# CDCDCDC_5V.net
KiCad netlist of a schematic drawn in Altium Designer
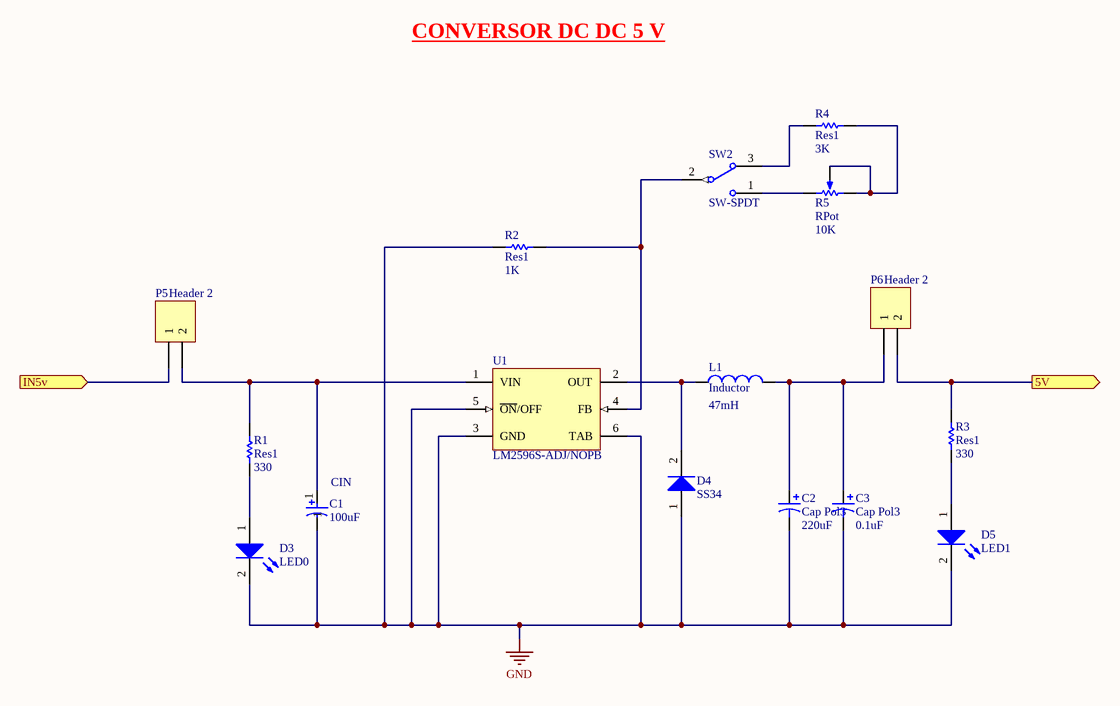
[diagram p0: CDCDCDC_5V.SchDoc]

(export (version "E")
  (design (tool "Eeschema 10.0.6"))
  (components
    (comp (ref "C1")
      (value "100uF")
      (footprint "NIC-UWT1H101MNL1GS_N")
      (fields (field (name "MANUFACTURER") "Nichicon"))
      (libsource (lib "Schlib1") (part "CMP-2000-07373-1"))
    )
    (comp (ref "C2")
      (value "Cap Pol3")
      (footprint "1812")
      (description "Polarized Capacitor (Surface Mount)")
      (fields (field (name "ALTIUM_VALUE") "220uF") (field (name "PUBLISHER") "Altium Limited"))
      (libsource (lib "Miscellaneous Devices") (part "Cap Pol3"))
    )
    (comp (ref "C3")
      (value "Cap Pol3")
      (footprint "1812")
      (description "Polarized Capacitor (Surface Mount)")
      (fields (field (name "ALTIUM_VALUE") "0.1uF") (field (name "PUBLISHER") "Altium Limited"))
      (libsource (lib "Miscellaneous Devices") (part "Cap Pol3"))
    )
    (comp (ref "D3")
      (value "LED0")
      (footprint "LED-0")
      (description "Typical INFRARED GaAs LED")
      (fields (field (name "PUBLISHER") "Altium Limited"))
      (libsource (lib "Miscellaneous Devices") (part "LED0"))
    )
    (comp (ref "D4")
      (value "SS34")
      (footprint "SMC")
      (description "Default Diode")
      (fields (field (name "PUBLISHER") "Altium Limited"))
      (libsource (lib "Miscellaneous Devices") (part "Diode"))
    )
    (comp (ref "D5")
      (value "LED1")
      (footprint "LED-0")
      (description "Typical INFRARED GaAs LED")
      (fields (field (name "PUBLISHER") "Altium Limited"))
      (libsource (lib "Miscellaneous Devices") (part "LED0"))
    )
    (comp (ref "L1")
      (value "Inductor")
      (footprint "0402-A")
      (fields (field (name "ALTIUM_VALUE") "47mH") (field (name "PUBLISHER") "Altium Limited"))
      (libsource (lib "Miscellaneous Devices") (part "Inductor"))
    )
    (comp (ref "P5")
      (value "Header 2")
      (footprint "HDR1X2")
      (description "Header, 2-Pin")
      (fields (field (name "PUBLISHER") "Altium Limited"))
      (libsource (lib "Miscellaneous Connectors") (part "Header 2"))
    )
    (comp (ref "P6")
      (value "Header 2")
      (footprint "HDR1X2")
      (description "Header, 2-Pin")
      (fields (field (name "PUBLISHER") "Altium Limited"))
      (libsource (lib "Miscellaneous Connectors") (part "Header 2"))
    )
    (comp (ref "R1")
      (value "Res1")
      (footprint "AXIAL-0.3")
      (description "Resistor")
      (fields (field (name "ALTIUM_VALUE") "330") (field (name "PUBLISHER") "Altium Limited"))
      (libsource (lib "Miscellaneous Devices") (part "Res1"))
    )
    (comp (ref "R2")
      (value "Res1")
      (footprint "AXIAL-0.3")
      (description "Resistor")
      (fields (field (name "ALTIUM_VALUE") "1K") (field (name "PUBLISHER") "Altium Limited"))
      (libsource (lib "Miscellaneous Devices") (part "Res1"))
    )
    (comp (ref "R3")
      (value "Res1")
      (footprint "AXIAL-0.3")
      (description "Resistor")
      (fields (field (name "ALTIUM_VALUE") "330") (field (name "PUBLISHER") "Altium Limited"))
      (libsource (lib "Miscellaneous Devices") (part "Res1"))
    )
    (comp (ref "R4")
      (value "Res1")
      (footprint "AXIAL-0.3")
      (description "Resistor")
      (fields (field (name "ALTIUM_VALUE") "3K") (field (name "PUBLISHER") "Altium Limited"))
      (libsource (lib "Miscellaneous Devices") (part "Res1"))
    )
    (comp (ref "R5")
      (value "RPot")
      (footprint "VR5")
      (description "Potentiometer")
      (fields (field (name "ALTIUM_VALUE") "10K") (field (name "PUBLISHER") "Altium Limited"))
      (libsource (lib "Miscellaneous Devices") (part "RPot"))
    )
    (comp (ref "SW2")
      (value "SW-SPDT")
      (footprint "TL36WW15050")
      (description "SPDT Subminiature Toggle Switch, Right Angle Mounting, Vertical Actuation")
      (fields (field (name "PUBLISHER") "Altium Limited"))
      (libsource (lib "Miscellaneous Devices") (part "SW-SPDT"))
    )
    (comp (ref "U1")
      (value "LM2596S-ADJ/NOPB")
      (footprint "KTT0005B_N")
      (description "SIMPLE SWITCHER® Power Converter 150 KHz 3A Step-Down Voltage Regulator, 5-pin TO-263, Pb-Free")
      (fields (field (name "MANUFACTURER") "Texas Instruments"))
      (libsource (lib "Schlib1") (part "CMP-0069-00271-3"))
    )
  )
  (nets
    (net (code "1") (name "/5V") (class "Default")
      (node (ref "P6") (pin "2") (pinfunction "2_2") (pintype "passive"))
      (node (ref "R3") (pin "2") (pinfunction "2_2") (pintype "passive"))
    )
    (net (code "2") (name "/IN5v") (class "Default")
      (node (ref "P5") (pin "1") (pinfunction "1_1") (pintype "passive"))
    )
    (net (code "3") (name "GND") (class "Default")
      (node (ref "C1") (pin "2") (pinfunction "2_2") (pintype "passive"))
      (node (ref "C2") (pin "2") (pinfunction "2_2") (pintype "passive"))
      (node (ref "C3") (pin "2") (pinfunction "2_2") (pintype "passive"))
      (node (ref "D3") (pin "2") (pinfunction "K_2") (pintype "passive"))
      (node (ref "D4") (pin "1") (pinfunction "A_1") (pintype "passive"))
      (node (ref "D5") (pin "2") (pinfunction "K_2") (pintype "passive"))
      (node (ref "R2") (pin "2") (pinfunction "2_2") (pintype "passive"))
      (node (ref "U1") (pin "3") (pinfunction "GND_3") (pintype "power_in"))
      (node (ref "U1") (pin "5") (pinfunction "~{ON}/OFF_5") (pintype "input"))
      (node (ref "U1") (pin "6") (pinfunction "TAB_6") (pintype "power_in"))
    )
    (net (code "4") (name "Net-(C2-Pad1)") (class "Default")
      (node (ref "C2") (pin "1") (pinfunction "1_1") (pintype "passive"))
      (node (ref "C3") (pin "1") (pinfunction "1_1") (pintype "passive"))
      (node (ref "L1") (pin "2") (pinfunction "2_2") (pintype "passive"))
      (node (ref "P6") (pin "1") (pinfunction "1_1") (pintype "passive"))
    )
    (net (code "5") (name "Net-(D3-A)") (class "Default")
      (node (ref "D3") (pin "1") (pinfunction "A_1") (pintype "passive"))
      (node (ref "R1") (pin "1") (pinfunction "1_1") (pintype "passive"))
    )
    (net (code "6") (name "Net-(D4-K)") (class "Default")
      (node (ref "D4") (pin "2") (pinfunction "K_2") (pintype "passive"))
      (node (ref "L1") (pin "1") (pinfunction "1_1") (pintype "passive"))
      (node (ref "U1") (pin "2") (pinfunction "OUT_2") (pintype "power_in"))
    )
    (net (code "7") (name "Net-(D5-A)") (class "Default")
      (node (ref "D5") (pin "1") (pinfunction "A_1") (pintype "passive"))
      (node (ref "R3") (pin "1") (pinfunction "1_1") (pintype "passive"))
    )
    (net (code "8") (name "Net-(R4-Pad2)") (class "Default")
      (node (ref "R4") (pin "2") (pinfunction "2_2") (pintype "passive"))
      (node (ref "SW2") (pin "3") (pinfunction "3_3") (pintype "passive"))
    )
    (net (code "9") (name "Net-(R5-BOT)") (class "Default")
      (node (ref "R5") (pin "2") (pinfunction "BOT_2") (pintype "passive"))
      (node (ref "SW2") (pin "1") (pinfunction "1_1") (pintype "passive"))
    )
    (net (code "10") (name "Net-(R5-TAP)") (class "Default")
      (node (ref "R4") (pin "1") (pinfunction "1_1") (pintype "passive"))
      (node (ref "R5") (pin "1") (pinfunction "TOP_1") (pintype "passive"))
      (node (ref "R5") (pin "3") (pinfunction "TAP_3") (pintype "passive"))
    )
    (net (code "11") (name "Net-(U1-FB)") (class "Default")
      (node (ref "R2") (pin "1") (pinfunction "1_1") (pintype "passive"))
      (node (ref "SW2") (pin "2") (pinfunction "2_2") (pintype "output"))
      (node (ref "U1") (pin "4") (pinfunction "FB_4") (pintype "input"))
    )
    (net (code "12") (name "Net-(U1-VIN)") (class "Default")
      (node (ref "C1") (pin "1") (pinfunction "1_1") (pintype "passive"))
      (node (ref "P5") (pin "2") (pinfunction "2_2") (pintype "passive"))
      (node (ref "R1") (pin "2") (pinfunction "2_2") (pintype "passive"))
      (node (ref "U1") (pin "1") (pinfunction "VIN_1") (pintype "power_in"))
    )
  )
)
